# 0_Charging_Module.net
KiCad netlist of a schematic drawn in Altium Designer
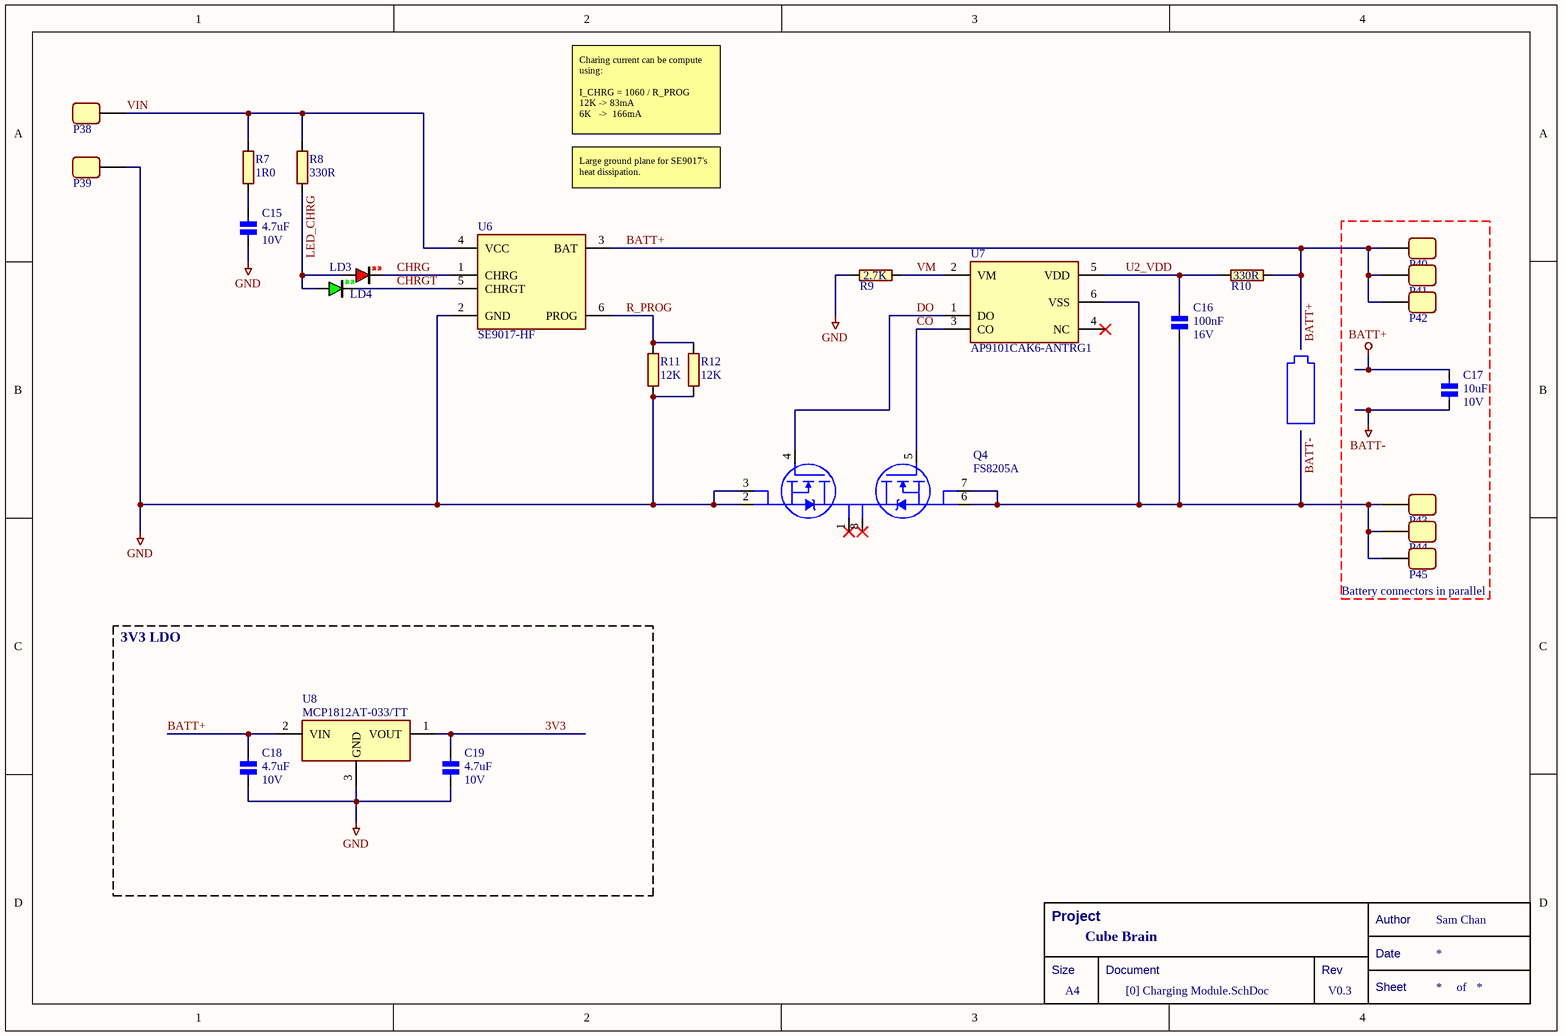
[diagram p0: [0] Charging Module.SchDoc]

(export (version "E")
  (design (tool "Eeschema 10.0.6"))
  (components
    (comp (ref "C15")
      (value "4.7uF")
      (footprint "CAPC0402X05N")
      (description "CAP CER 4.7UF 10V X5R 0402")
      (fields
        (field (name "MANUFACTURER") "Samsung Electro-Mechanics")
        (field (name "MANUFACTURER PART NUMBER") "CL05A475MP5NRNC")
        (field (name "CAPACITANCE") "4.7uF")
        (field (name "VOLTAGE - RATED") "10V")
      )
      (libsource (lib "Cube Library") (part "CER 4.7UF 10V"))
    )
    (comp (ref "C16")
      (value "100nF")
      (footprint "CAPC0402X05N")
      (description "CAP CER 0.1UF 16V X7R 0402")
      (fields
        (field (name "MANUFACTURER") "Samsung Electro-Mechanics")
        (field (name "MANUFACTURER PART NUMBER") "CL05B104KO5NNNC")
        (field (name "CAPACITANCE") "100nF")
        (field (name "VOLTAGE - RATED") "16V")
      )
      (libsource (lib "Cube Library") (part "CER 100NF 16V"))
    )
    (comp (ref "C17")
      (value "10uF")
      (footprint "CAPC0402X05N")
      (description "CAP CER 10UF 10V X5R 0402")
      (fields
        (field (name "MANUFACTURER") "Murata Electronics")
        (field (name "MANUFACTURER PART NUMBER") "GRM155R61A106ME44D")
        (field (name "CAPACITANCE") "10uF")
        (field (name "VOLTAGE - RATED") "10V")
      )
      (libsource (lib "Cube Library") (part "CER 10UF 10V"))
    )
    (comp (ref "C18")
      (value "4.7uF")
      (footprint "CAPC0402X05N")
      (description "CAP CER 4.7UF 10V X5R 0402")
      (fields
        (field (name "MANUFACTURER") "Samsung Electro-Mechanics")
        (field (name "MANUFACTURER PART NUMBER") "CL05A475MP5NRNC")
        (field (name "CAPACITANCE") "4.7uF")
        (field (name "VOLTAGE - RATED") "10V")
      )
      (libsource (lib "Cube Library") (part "CER 4.7UF 10V"))
    )
    (comp (ref "C19")
      (value "4.7uF")
      (footprint "CAPC0402X05N")
      (description "CAP CER 4.7UF 10V X5R 0402")
      (fields
        (field (name "MANUFACTURER") "Samsung Electro-Mechanics")
        (field (name "MANUFACTURER PART NUMBER") "CL05A475MP5NRNC")
        (field (name "CAPACITANCE") "4.7uF")
        (field (name "VOLTAGE - RATED") "10V")
      )
      (libsource (lib "Cube Library") (part "CER 4.7UF 10V"))
    )
    (comp (ref "LD3")
      (value "Red")
      (footprint "LEDM0603X08N_RED")
      (description "LED RED CLEAR CHIP SMD")
      (fields
        (field (name "MANUFACTURER") "Lite-On Inc.")
        (field (name "MANUFACTURER PART NUMBER") "LTST-C190KRKT")
      )
      (libsource (lib "Cube Library") (part "LED 0603 RED"))
    )
    (comp (ref "LD4")
      (value "Green")
      (footprint "LEDM0603X08N_GREEN")
      (description "LED GREEN CLEAR CHIP SMD")
      (fields
        (field (name "MANUFACTURER") "Lite-On Inc.")
        (field (name "MANUFACTURER PART NUMBER") "LTST-C190KGKT")
      )
      (libsource (lib "Cube Library") (part "LED 0603 GREEN"))
    )
    (comp (ref "P38")
      (value "PAD_4")
      (footprint "PAD_0.5X1MM")
      (description "a Rec pad, 0.5X1mm")
      (libsource (lib "Cube Library") (part "PAD_4"))
    )
    (comp (ref "P39")
      (value "PAD_4")
      (footprint "PAD_0.5X1MM")
      (description "a Rec pad, 0.5X1mm")
      (libsource (lib "Cube Library") (part "PAD_4"))
    )
    (comp (ref "P40")
      (value "PAD_4")
      (footprint "PAD_0.5X1MM")
      (description "a Rec pad, 0.5X1mm")
      (libsource (lib "Cube Library") (part "PAD_4"))
    )
    (comp (ref "P41")
      (value "PAD_4")
      (footprint "PAD_0.5X1MM")
      (description "a Rec pad, 0.5X1mm")
      (libsource (lib "Cube Library") (part "PAD_4"))
    )
    (comp (ref "P42")
      (value "PAD_4")
      (footprint "PAD_0.5X1MM")
      (description "a Rec pad, 0.5X1mm")
      (libsource (lib "Cube Library") (part "PAD_4"))
    )
    (comp (ref "P43")
      (value "PAD_4")
      (footprint "PAD_0.5X1MM")
      (description "a Rec pad, 0.5X1mm")
      (libsource (lib "Cube Library") (part "PAD_4"))
    )
    (comp (ref "P44")
      (value "PAD_4")
      (footprint "PAD_0.5X1MM")
      (description "a Rec pad, 0.5X1mm")
      (libsource (lib "Cube Library") (part "PAD_4"))
    )
    (comp (ref "P45")
      (value "PAD_4")
      (footprint "PAD_0.5X1MM")
      (description "a Rec pad, 0.5X1mm")
      (libsource (lib "Cube Library") (part "PAD_4"))
    )
    (comp (ref "Q4")
      (value "FS8205A")
      (footprint "FS8205A")
      (description "MOSFET 2N-CH 20V 6A TSSOP8")
      (fields (field (name "MANUFACTURER") "Fortune Semicon"))
      (libsource (lib "Cube Library") (part "FS8205A"))
    )
    (comp (ref "R7")
      (value "1R0")
      (footprint "RESC0402X04N")
      (description "RES SMD 11RK OHM 1% 1/16W 0402")
      (fields
        (field (name "MANUFACTURER") "YAGEO")
        (field (name "MANUFACTURER PART NUMBER") "RC0402FR-071RL")
        (field (name "RESISTANCE") "1R0")
      )
      (libsource (lib "Cube Library") (part "RES 1R"))
    )
    (comp (ref "R8")
      (value "330R")
      (footprint "RESC0402X04N")
      (description "RES SMD 330R OHM 1% 1/16W 0402")
      (fields
        (field (name "MANUFACTURER") "YAGEO")
        (field (name "MANUFACTURER PART NUMBER") "RC0402FR-07330RL")
        (field (name "RESISTANCE") "330R")
      )
      (libsource (lib "") (part "RES 330R_1"))
    )
    (comp (ref "R9")
      (value "2.7K")
      (footprint "RESC0402X04N")
      (description "RES SMD 2.7K OHM 1% 1/16W 0402")
      (fields
        (field (name "MANUFACTURER") "YAGEO")
        (field (name "MANUFACTURER PART NUMBER") "AC0402FR-072K7L")
        (field (name "RESISTANCE") "2.7K")
      )
      (libsource (lib "Cube Library") (part "RES 2.7K"))
    )
    (comp (ref "R10")
      (value "330R")
      (footprint "RESC0402X04N")
      (description "RES SMD 330R OHM 1% 1/16W 0402")
      (fields
        (field (name "MANUFACTURER") "YAGEO")
        (field (name "MANUFACTURER PART NUMBER") "RC0402FR-07330RL")
        (field (name "RESISTANCE") "330R")
      )
      (libsource (lib "Cube Library") (part "RES 330R"))
    )
    (comp (ref "R11")
      (value "12K")
      (footprint "RESC0402X04N")
      (description "RES SMD 12K OHM 1% 1/16W 0402")
      (fields
        (field (name "MANUFACTURER") "YAGEO")
        (field (name "MANUFACTURER PART NUMBER") "RC0402FR-0712KL")
        (field (name "RESISTANCE") "12K")
      )
      (libsource (lib "Cube Library") (part "RES 12K"))
    )
    (comp (ref "R12")
      (value "12K")
      (footprint "RESC0402X04N")
      (description "RES SMD 12K OHM 1% 1/16W 0402")
      (fields
        (field (name "MANUFACTURER") "YAGEO")
        (field (name "MANUFACTURER PART NUMBER") "RC0402FR-0712KL")
        (field (name "RESISTANCE") "12K")
      )
      (libsource (lib "Cube Library") (part "RES 12K"))
    )
    (comp (ref "U6")
      (value "SE9017-HF")
      (footprint "SE9017-HF")
      (description "IC LI-ION/LI-POLY CTRLR SOT23-6")
      (fields (field (name "MANUFACTURER") "Seaward Elec"))
      (libsource (lib "Cube Library") (part "SE9017-HF"))
    )
    (comp (ref "U7")
      (value "AP9101CAK6-ANTRG1")
      (footprint "AP9101CAK6")
      (description "IC BATT PROT LI-ION 1-CELL SOT26")
      (fields (field (name "MANUFACTURER") "Diodes Incorporated"))
      (libsource (lib "Cube Library") (part "AP9101CAK6-ANTRG1"))
    )
    (comp (ref "U8")
      (value "MCP1812AT-033/TT")
      (footprint "MCP1812AT-033/TT")
      (description "IC REG LINEAR 3.3V 300MA SOT23-3")
      (fields (field (name "MANUFACTURER") "Microchip Technology"))
      (libsource (lib "Cube Library") (part "MCP1812AT-033/TT"))
    )
  )
  (nets
    (net (code "1") (name "/3V3") (class "Default")
      (node (ref "C19") (pin "1") (pinfunction "1_1") (pintype "passive"))
      (node (ref "U8") (pin "1") (pinfunction "VOUT_1") (pintype "passive"))
    )
    (net (code "2") (name "/CHRG") (class "Default")
      (node (ref "LD3") (pin "2") (pinfunction "2_2") (pintype "passive"))
      (node (ref "U6") (pin "1") (pinfunction "CHRG_1") (pintype "passive"))
    )
    (net (code "3") (name "/CHRGT") (class "Default")
      (node (ref "LD4") (pin "2") (pinfunction "2_2") (pintype "passive"))
      (node (ref "U6") (pin "5") (pinfunction "CHRGT_5") (pintype "passive"))
    )
    (net (code "4") (name "/CO") (class "Default")
      (node (ref "Q4") (pin "5") (pinfunction "G2_5") (pintype "passive"))
      (node (ref "U7") (pin "3") (pinfunction "CO_3") (pintype "passive"))
    )
    (net (code "5") (name "/DO") (class "Default")
      (node (ref "Q4") (pin "4") (pinfunction "G1_4") (pintype "passive"))
      (node (ref "U7") (pin "1") (pinfunction "DO_1") (pintype "passive"))
    )
    (net (code "6") (name "/LED_CHRG") (class "Default")
      (node (ref "LD3") (pin "1") (pinfunction "1_1") (pintype "passive"))
      (node (ref "LD4") (pin "1") (pinfunction "1_1") (pintype "passive"))
      (node (ref "R8") (pin "1") (pinfunction "1_1") (pintype "passive"))
    )
    (net (code "7") (name "/R_PROG") (class "Default")
      (node (ref "R11") (pin "1") (pinfunction "1_1") (pintype "passive"))
      (node (ref "R12") (pin "1") (pinfunction "1_1") (pintype "passive"))
      (node (ref "U6") (pin "6") (pinfunction "PROG_6") (pintype "passive"))
    )
    (net (code "8") (name "/U2_VDD") (class "Default")
      (node (ref "C16") (pin "1") (pinfunction "1_1") (pintype "passive"))
      (node (ref "R10") (pin "1") (pinfunction "1_1") (pintype "passive"))
      (node (ref "U7") (pin "5") (pinfunction "VDD_5") (pintype "passive"))
    )
    (net (code "9") (name "/VIN") (class "Default")
      (node (ref "P38") (pin "1") (pinfunction "1_1") (pintype "passive"))
      (node (ref "R7") (pin "2") (pinfunction "2_2") (pintype "passive"))
      (node (ref "R8") (pin "2") (pinfunction "2_2") (pintype "passive"))
      (node (ref "U6") (pin "4") (pinfunction "VCC_4") (pintype "passive"))
    )
    (net (code "10") (name "/VM") (class "Default")
      (node (ref "R9") (pin "2") (pinfunction "2_2") (pintype "passive"))
      (node (ref "U7") (pin "2") (pinfunction "VM_2") (pintype "passive"))
    )
    (net (code "11") (name "BATT+") (class "Default")
      (node (ref "C17") (pin "1") (pinfunction "1_1") (pintype "passive"))
      (node (ref "C18") (pin "1") (pinfunction "1_1") (pintype "passive"))
      (node (ref "P40") (pin "1") (pinfunction "1_1") (pintype "passive"))
      (node (ref "P41") (pin "1") (pinfunction "1_1") (pintype "passive"))
      (node (ref "P42") (pin "1") (pinfunction "1_1") (pintype "passive"))
      (node (ref "R10") (pin "2") (pinfunction "2_2") (pintype "passive"))
      (node (ref "U6") (pin "3") (pinfunction "BAT_3") (pintype "passive"))
      (node (ref "U8") (pin "2") (pinfunction "VIN_2") (pintype "passive"))
    )
    (net (code "12") (name "BATT-") (class "Default")
      (node (ref "C16") (pin "2") (pinfunction "2_2") (pintype "passive"))
      (node (ref "C17") (pin "2") (pinfunction "2_2") (pintype "passive"))
      (node (ref "P43") (pin "1") (pinfunction "1_1") (pintype "passive"))
      (node (ref "P44") (pin "1") (pinfunction "1_1") (pintype "passive"))
      (node (ref "P45") (pin "1") (pinfunction "1_1") (pintype "passive"))
      (node (ref "Q4") (pin "6") (pinfunction "S2_6") (pintype "passive"))
      (node (ref "Q4") (pin "7") (pinfunction "S2_7") (pintype "passive"))
      (node (ref "U7") (pin "6") (pinfunction "VSS_6") (pintype "passive"))
    )
    (net (code "13") (name "GND") (class "Default")
      (node (ref "C15") (pin "2") (pinfunction "2_2") (pintype "passive"))
      (node (ref "C18") (pin "2") (pinfunction "2_2") (pintype "passive"))
      (node (ref "C19") (pin "2") (pinfunction "2_2") (pintype "passive"))
      (node (ref "P39") (pin "1") (pinfunction "1_1") (pintype "passive"))
      (node (ref "Q4") (pin "2") (pinfunction "S1_2") (pintype "passive"))
      (node (ref "Q4") (pin "3") (pinfunction "S1_3") (pintype "passive"))
      (node (ref "R11") (pin "2") (pinfunction "2_2") (pintype "passive"))
      (node (ref "R12") (pin "2") (pinfunction "2_2") (pintype "passive"))
      (node (ref "R9") (pin "1") (pinfunction "1_1") (pintype "passive"))
      (node (ref "U6") (pin "2") (pinfunction "GND_2") (pintype "passive"))
      (node (ref "U8") (pin "3") (pinfunction "GND_3") (pintype "passive"))
    )
    (net (code "14") (name "Net-(C15-Pad1)") (class "Default")
      (node (ref "C15") (pin "1") (pinfunction "1_1") (pintype "passive"))
      (node (ref "R7") (pin "1") (pinfunction "1_1") (pintype "passive"))
    )
    (net (code "15") (name "unconnected-(Q4-D12-Pad1)") (class "Default")
      (node (ref "Q4") (pin "1") (pinfunction "D12_1") (pintype "passive+no_connect"))
    )
    (net (code "16") (name "unconnected-(Q4-D12-Pad8)") (class "Default")
      (node (ref "Q4") (pin "8") (pinfunction "D12_8") (pintype "passive+no_connect"))
    )
    (net (code "17") (name "unconnected-(U7-NC-Pad4)") (class "Default")
      (node (ref "U7") (pin "4") (pinfunction "NC_4") (pintype "passive+no_connect"))
    )
  )
)
